# Tray2_Comms_Beacon.net
KiCad netlist of a schematic drawn in Altium Designer
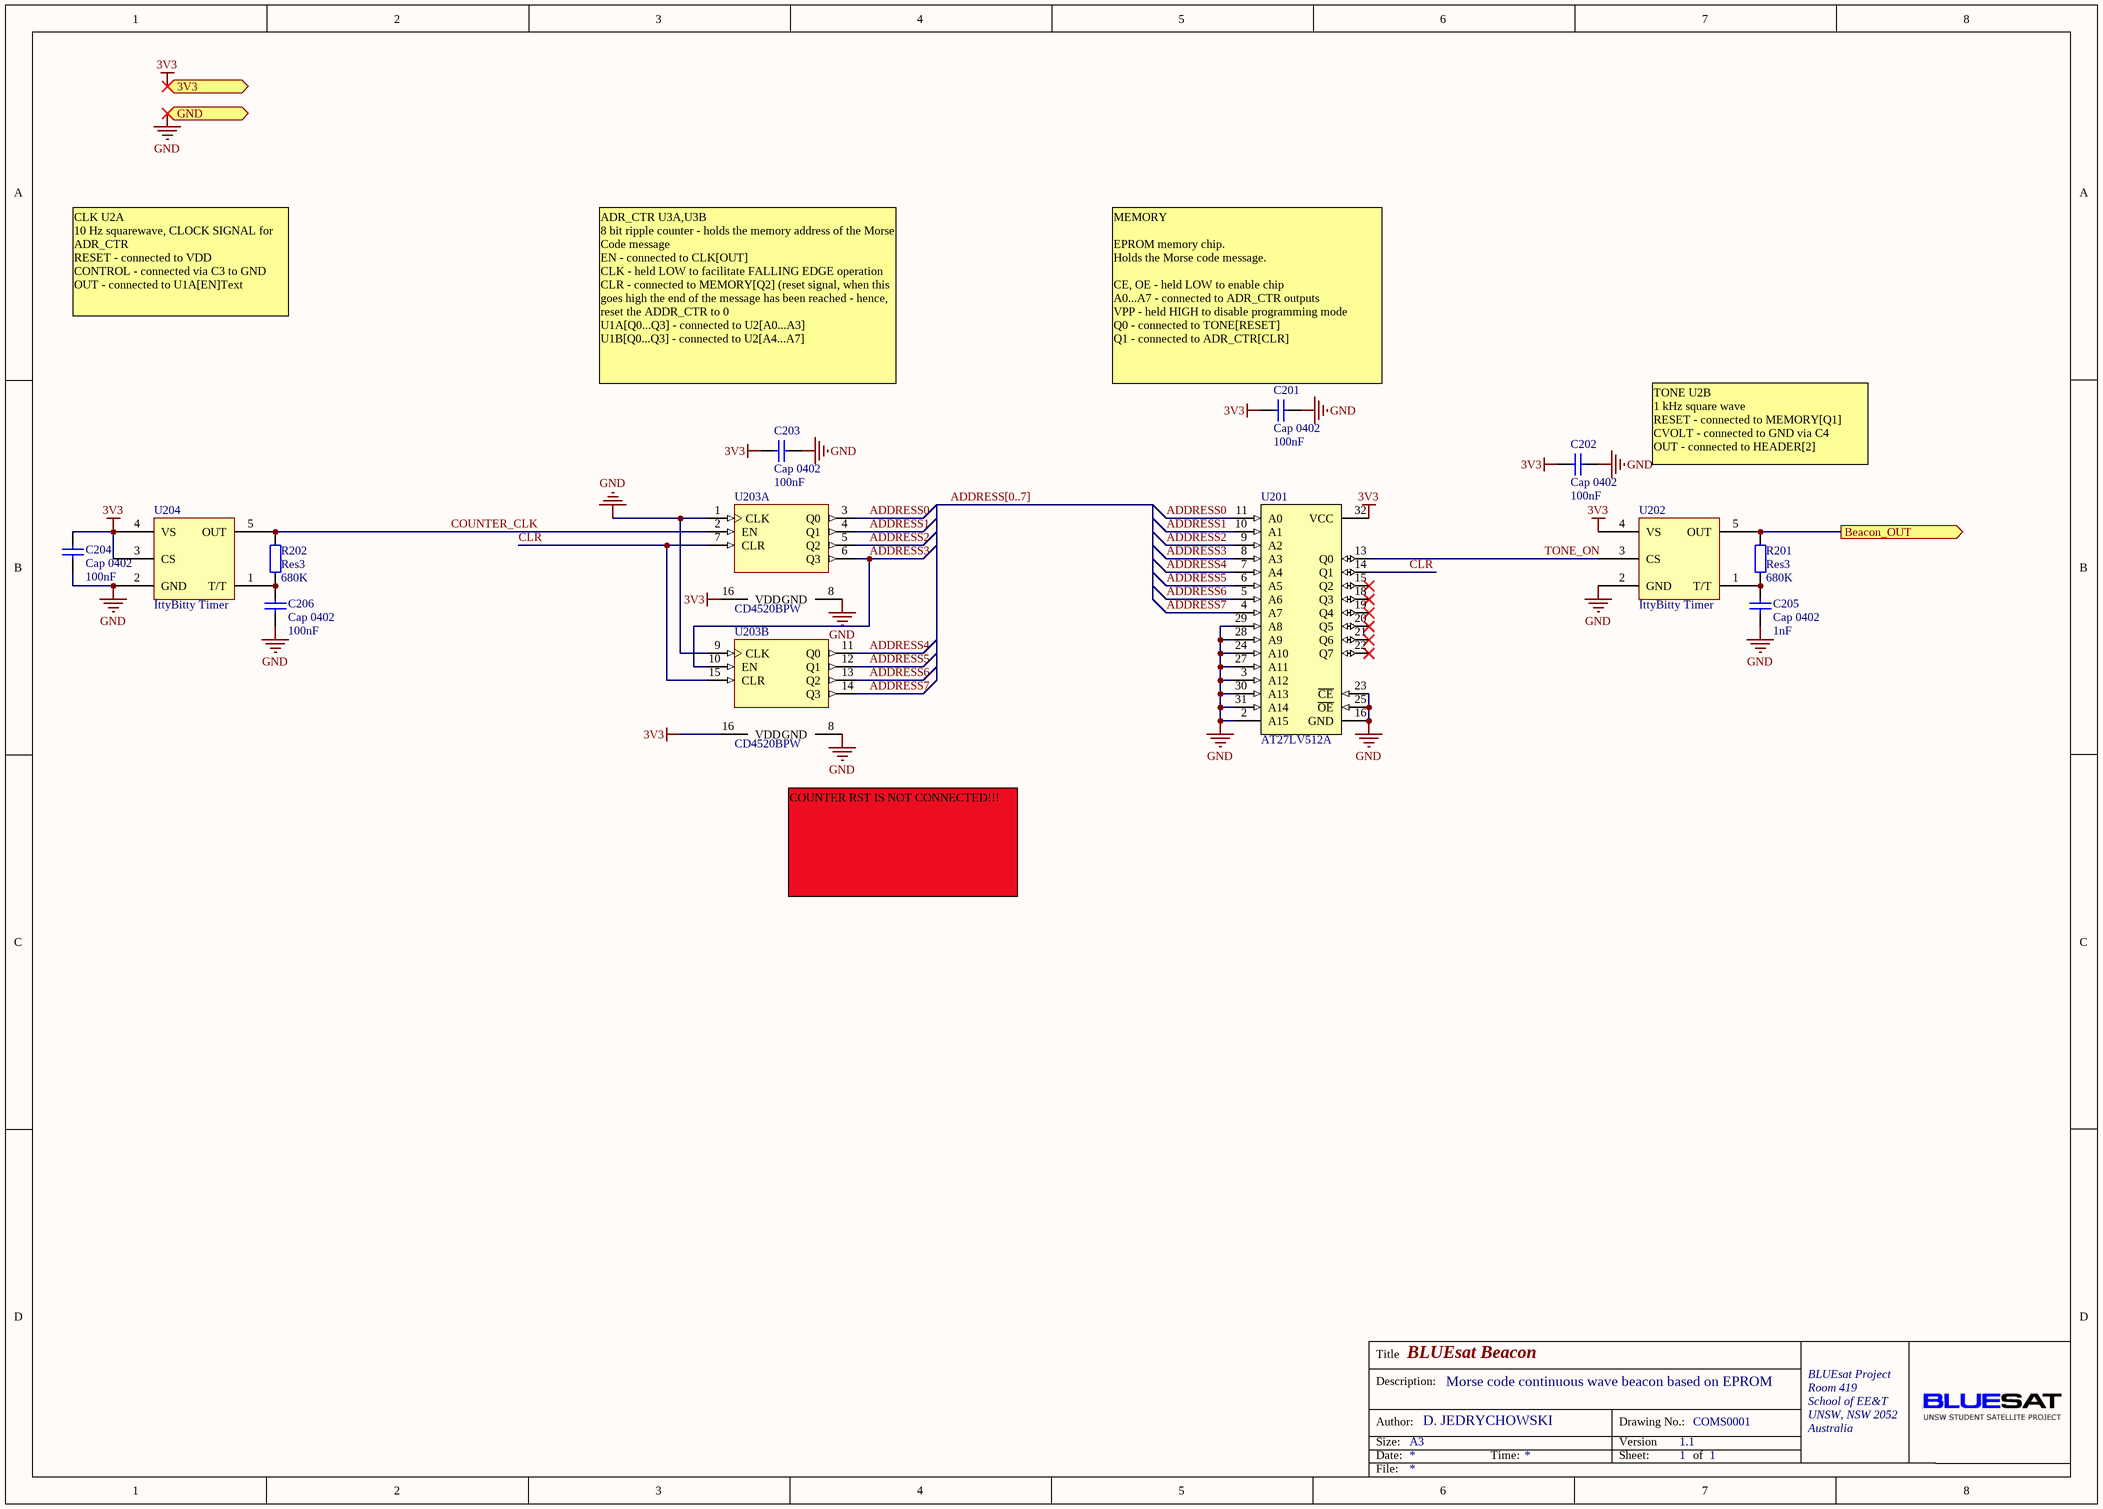
[diagram p0: Tray2_Comms_Beacon.SchDoc]

(export (version "E")
  (design (tool "Eeschema 10.0.6"))
  (components
    (comp (ref "C201")
      (value "Cap 0402")
      (footprint "CAPC1005X06L")
      (description "Capacitor")
      (fields (field (name "ALTIUM_VALUE") "100nF") (field (name "PUBLISHER") "Altium Limited"))
      (libsource (lib "CSC") (part "Cap 0402"))
    )
    (comp (ref "C202")
      (value "Cap 0402")
      (footprint "CAPC1005X06L")
      (description "Capacitor")
      (fields (field (name "ALTIUM_VALUE") "100nF") (field (name "PUBLISHER") "Altium Limited"))
      (libsource (lib "CSC") (part "Cap 0402"))
    )
    (comp (ref "C203")
      (value "Cap 0402")
      (footprint "CAPC1005X06L")
      (description "Capacitor")
      (fields (field (name "ALTIUM_VALUE") "100nF") (field (name "PUBLISHER") "Altium Limited"))
      (libsource (lib "CSC") (part "Cap 0402"))
    )
    (comp (ref "C204")
      (value "Cap 0402")
      (footprint "CAPC1005X06L")
      (description "Capacitor")
      (fields (field (name "ALTIUM_VALUE") "100nF") (field (name "PUBLISHER") "Altium Limited"))
      (libsource (lib "CSC") (part "Cap 0402"))
    )
    (comp (ref "C205")
      (value "Cap 0402")
      (footprint "CAPC1005X06L")
      (description "Capacitor")
      (fields (field (name "ALTIUM_VALUE") "1nF") (field (name "PUBLISHER") "Altium Limited"))
      (libsource (lib "CSC") (part "Cap 0402"))
    )
    (comp (ref "C206")
      (value "Cap 0402")
      (footprint "CAPC1005X06L")
      (description "Capacitor")
      (fields (field (name "ALTIUM_VALUE") "100nF") (field (name "PUBLISHER") "Altium Limited"))
      (libsource (lib "CSC") (part "Cap 0402"))
    )
    (comp (ref "R201")
      (value "Res3")
      (footprint "RESC1005X06L")
      (description "Resistor")
      (fields (field (name "ALTIUM_VALUE") "680K") (field (name "PUBLISHER") "Altium Limited"))
      (libsource (lib "CSC") (part "Res3"))
    )
    (comp (ref "R202")
      (value "Res3")
      (footprint "RESC1005X06L")
      (description "Resistor")
      (fields (field (name "ALTIUM_VALUE") "680K") (field (name "PUBLISHER") "Altium Limited"))
      (libsource (lib "CSC") (part "Res3"))
    )
    (comp (ref "U201")
      (value "AT27LV512A")
      (footprint "Comms Board Small Footprints:PLCC7*9")
      (description "512 Kbit (32Kb X 8) UV EPROM and OTP EPROM")
      (fields (field (name "PUBLISHER") "Altium Limited"))
      (libsource (lib "Comms Board Small Footprints") (part "AT27LV512A"))
    )
    (comp (ref "U202")
      (value "IttyBitty Timer")
      (footprint "Comms Board Small Footprints:SOT23-5")
      (description "Miniature Astable Timer Chip")
      (libsource (lib "Comms Board Small Footprints") (part "MIC1557"))
    )
    (comp (ref "U203")
      (value "CD4520BPW")
      (footprint "TSSOP16")
      (description "Dual Binary Up-Counter")
      (libsource (lib "Comms Board Small Footprints") (part "CD4520BPW"))
    )
    (comp (ref "U204")
      (value "IttyBitty Timer")
      (footprint "Comms Board Small Footprints:SOT23-5")
      (description "Miniature Astable Timer Chip")
      (libsource (lib "Comms Board Small Footprints") (part "MIC1557"))
    )
  )
  (nets
    (net (code "1") (name "/ADDRESS0") (class "Default")
      (node (ref "U201") (pin "11") (pinfunction "A0_11") (pintype "input"))
      (node (ref "U203") (pin "3") (pinfunction "Q0_3") (pintype "output"))
    )
    (net (code "2") (name "/ADDRESS1") (class "Default")
      (node (ref "U201") (pin "10") (pinfunction "A1_10") (pintype "input"))
      (node (ref "U203") (pin "4") (pinfunction "Q1_4") (pintype "output"))
    )
    (net (code "3") (name "/ADDRESS2") (class "Default")
      (node (ref "U201") (pin "9") (pinfunction "A2_9") (pintype "input"))
      (node (ref "U203") (pin "5") (pinfunction "Q2_5") (pintype "output"))
    )
    (net (code "4") (name "/ADDRESS3") (class "Default")
      (node (ref "U201") (pin "8") (pinfunction "A3_8") (pintype "input"))
      (node (ref "U203") (pin "10") (pinfunction "EN_10") (pintype "input"))
      (node (ref "U203") (pin "6") (pinfunction "Q3_6") (pintype "output"))
    )
    (net (code "5") (name "/ADDRESS4") (class "Default")
      (node (ref "U201") (pin "7") (pinfunction "A4_7") (pintype "input"))
      (node (ref "U203") (pin "11") (pinfunction "Q0_11") (pintype "output"))
    )
    (net (code "6") (name "/ADDRESS5") (class "Default")
      (node (ref "U201") (pin "6") (pinfunction "A5_6") (pintype "input"))
      (node (ref "U203") (pin "12") (pinfunction "Q1_12") (pintype "output"))
    )
    (net (code "7") (name "/ADDRESS6") (class "Default")
      (node (ref "U201") (pin "5") (pinfunction "A6_5") (pintype "input"))
      (node (ref "U203") (pin "13") (pinfunction "Q2_13") (pintype "output"))
    )
    (net (code "8") (name "/ADDRESS7") (class "Default")
      (node (ref "U201") (pin "4") (pinfunction "A7_4") (pintype "input"))
      (node (ref "U203") (pin "14") (pinfunction "Q3_14") (pintype "output"))
    )
    (net (code "10") (name "/Beacon_OUT") (class "Default")
      (node (ref "R201") (pin "1") (pinfunction "1_1") (pintype "passive"))
      (node (ref "U202") (pin "5") (pinfunction "OUT_5") (pintype "passive"))
    )
    (net (code "11") (name "/CLR") (class "Default")
      (node (ref "U201") (pin "14") (pinfunction "Q1_14") (pintype "bidirectional"))
      (node (ref "U203") (pin "15") (pinfunction "CLR_15") (pintype "input"))
      (node (ref "U203") (pin "7") (pinfunction "CLR_7") (pintype "input"))
    )
    (net (code "12") (name "/COUNTER_CLK") (class "Default")
      (node (ref "R202") (pin "1") (pinfunction "1_1") (pintype "passive"))
      (node (ref "U203") (pin "2") (pinfunction "EN_2") (pintype "input"))
      (node (ref "U204") (pin "5") (pinfunction "OUT_5") (pintype "passive"))
    )
    (net (code "13") (name "/TONE_ON") (class "Default")
      (node (ref "U201") (pin "13") (pinfunction "Q0_13") (pintype "bidirectional"))
      (node (ref "U202") (pin "3") (pinfunction "CS_3") (pintype "passive"))
    )
    (net (code "14") (name "3V3") (class "Default")
      (node (ref "C201") (pin "1") (pinfunction "1_1") (pintype "passive"))
      (node (ref "C202") (pin "1") (pinfunction "1_1") (pintype "passive"))
      (node (ref "C203") (pin "1") (pinfunction "1_1") (pintype "passive"))
      (node (ref "C204") (pin "2") (pinfunction "2_2") (pintype "passive"))
      (node (ref "U201") (pin "32") (pinfunction "VCC_32") (pintype "power_in"))
      (node (ref "U202") (pin "4") (pinfunction "VS_4") (pintype "passive"))
      (node (ref "U203") (pin "16") (pinfunction "VDD_16") (pintype "power_in"))
      (node (ref "U204") (pin "3") (pinfunction "CS_3") (pintype "passive"))
      (node (ref "U204") (pin "4") (pinfunction "VS_4") (pintype "passive"))
    )
    (net (code "15") (name "GND") (class "Default")
      (node (ref "C201") (pin "2") (pinfunction "2_2") (pintype "passive"))
      (node (ref "C202") (pin "2") (pinfunction "2_2") (pintype "passive"))
      (node (ref "C203") (pin "2") (pinfunction "2_2") (pintype "passive"))
      (node (ref "C204") (pin "1") (pinfunction "1_1") (pintype "passive"))
      (node (ref "C205") (pin "1") (pinfunction "1_1") (pintype "passive"))
      (node (ref "C206") (pin "1") (pinfunction "1_1") (pintype "passive"))
      (node (ref "U201") (pin "16") (pinfunction "GND_16") (pintype "power_in"))
      (node (ref "U201") (pin "2") (pinfunction "A15_2") (pintype "passive"))
      (node (ref "U201") (pin "23") (pinfunction "~{CE}_23") (pintype "input"))
      (node (ref "U201") (pin "24") (pinfunction "A10_24") (pintype "input"))
      (node (ref "U201") (pin "25") (pinfunction "~{OE}_25") (pintype "input"))
      (node (ref "U201") (pin "27") (pinfunction "A11_27") (pintype "input"))
      (node (ref "U201") (pin "28") (pinfunction "A9_28") (pintype "input"))
      (node (ref "U201") (pin "29") (pinfunction "A8_29") (pintype "input"))
      (node (ref "U201") (pin "3") (pinfunction "A12_3") (pintype "input"))
      (node (ref "U201") (pin "30") (pinfunction "A13_30") (pintype "input"))
      (node (ref "U201") (pin "31") (pinfunction "A14_31") (pintype "input"))
      (node (ref "U202") (pin "2") (pinfunction "GND_2") (pintype "passive"))
      (node (ref "U203") (pin "1") (pinfunction "CLK_1") (pintype "input"))
      (node (ref "U203") (pin "8") (pinfunction "GND_8") (pintype "power_in"))
      (node (ref "U203") (pin "9") (pinfunction "CLK_9") (pintype "input"))
      (node (ref "U204") (pin "2") (pinfunction "GND_2") (pintype "passive"))
    )
    (net (code "16") (name "Net-(U202-T{slash}T)") (class "Default")
      (node (ref "C205") (pin "2") (pinfunction "2_2") (pintype "passive"))
      (node (ref "R201") (pin "2") (pinfunction "2_2") (pintype "passive"))
      (node (ref "U202") (pin "1") (pinfunction "T/T_1") (pintype "passive"))
    )
    (net (code "17") (name "Net-(U204-T{slash}T)") (class "Default")
      (node (ref "C206") (pin "2") (pinfunction "2_2") (pintype "passive"))
      (node (ref "R202") (pin "2") (pinfunction "2_2") (pintype "passive"))
      (node (ref "U204") (pin "1") (pinfunction "T/T_1") (pintype "passive"))
    )
    (net (code "18") (name "unconnected-(U201-Q2-Pad15)") (class "Default")
      (node (ref "U201") (pin "15") (pinfunction "Q2_15") (pintype "bidirectional+no_connect"))
    )
    (net (code "19") (name "unconnected-(U201-Q3-Pad18)") (class "Default")
      (node (ref "U201") (pin "18") (pinfunction "Q3_18") (pintype "bidirectional+no_connect"))
    )
    (net (code "20") (name "unconnected-(U201-Q4-Pad19)") (class "Default")
      (node (ref "U201") (pin "19") (pinfunction "Q4_19") (pintype "bidirectional+no_connect"))
    )
    (net (code "21") (name "unconnected-(U201-Q5-Pad20)") (class "Default")
      (node (ref "U201") (pin "20") (pinfunction "Q5_20") (pintype "bidirectional+no_connect"))
    )
    (net (code "22") (name "unconnected-(U201-Q6-Pad21)") (class "Default")
      (node (ref "U201") (pin "21") (pinfunction "Q6_21") (pintype "bidirectional+no_connect"))
    )
    (net (code "23") (name "unconnected-(U201-Q7-Pad22)") (class "Default")
      (node (ref "U201") (pin "22") (pinfunction "Q7_22") (pintype "bidirectional+no_connect"))
    )
  )
)
